# XBeeV2.net
KiCad netlist of a schematic drawn in EAGLE
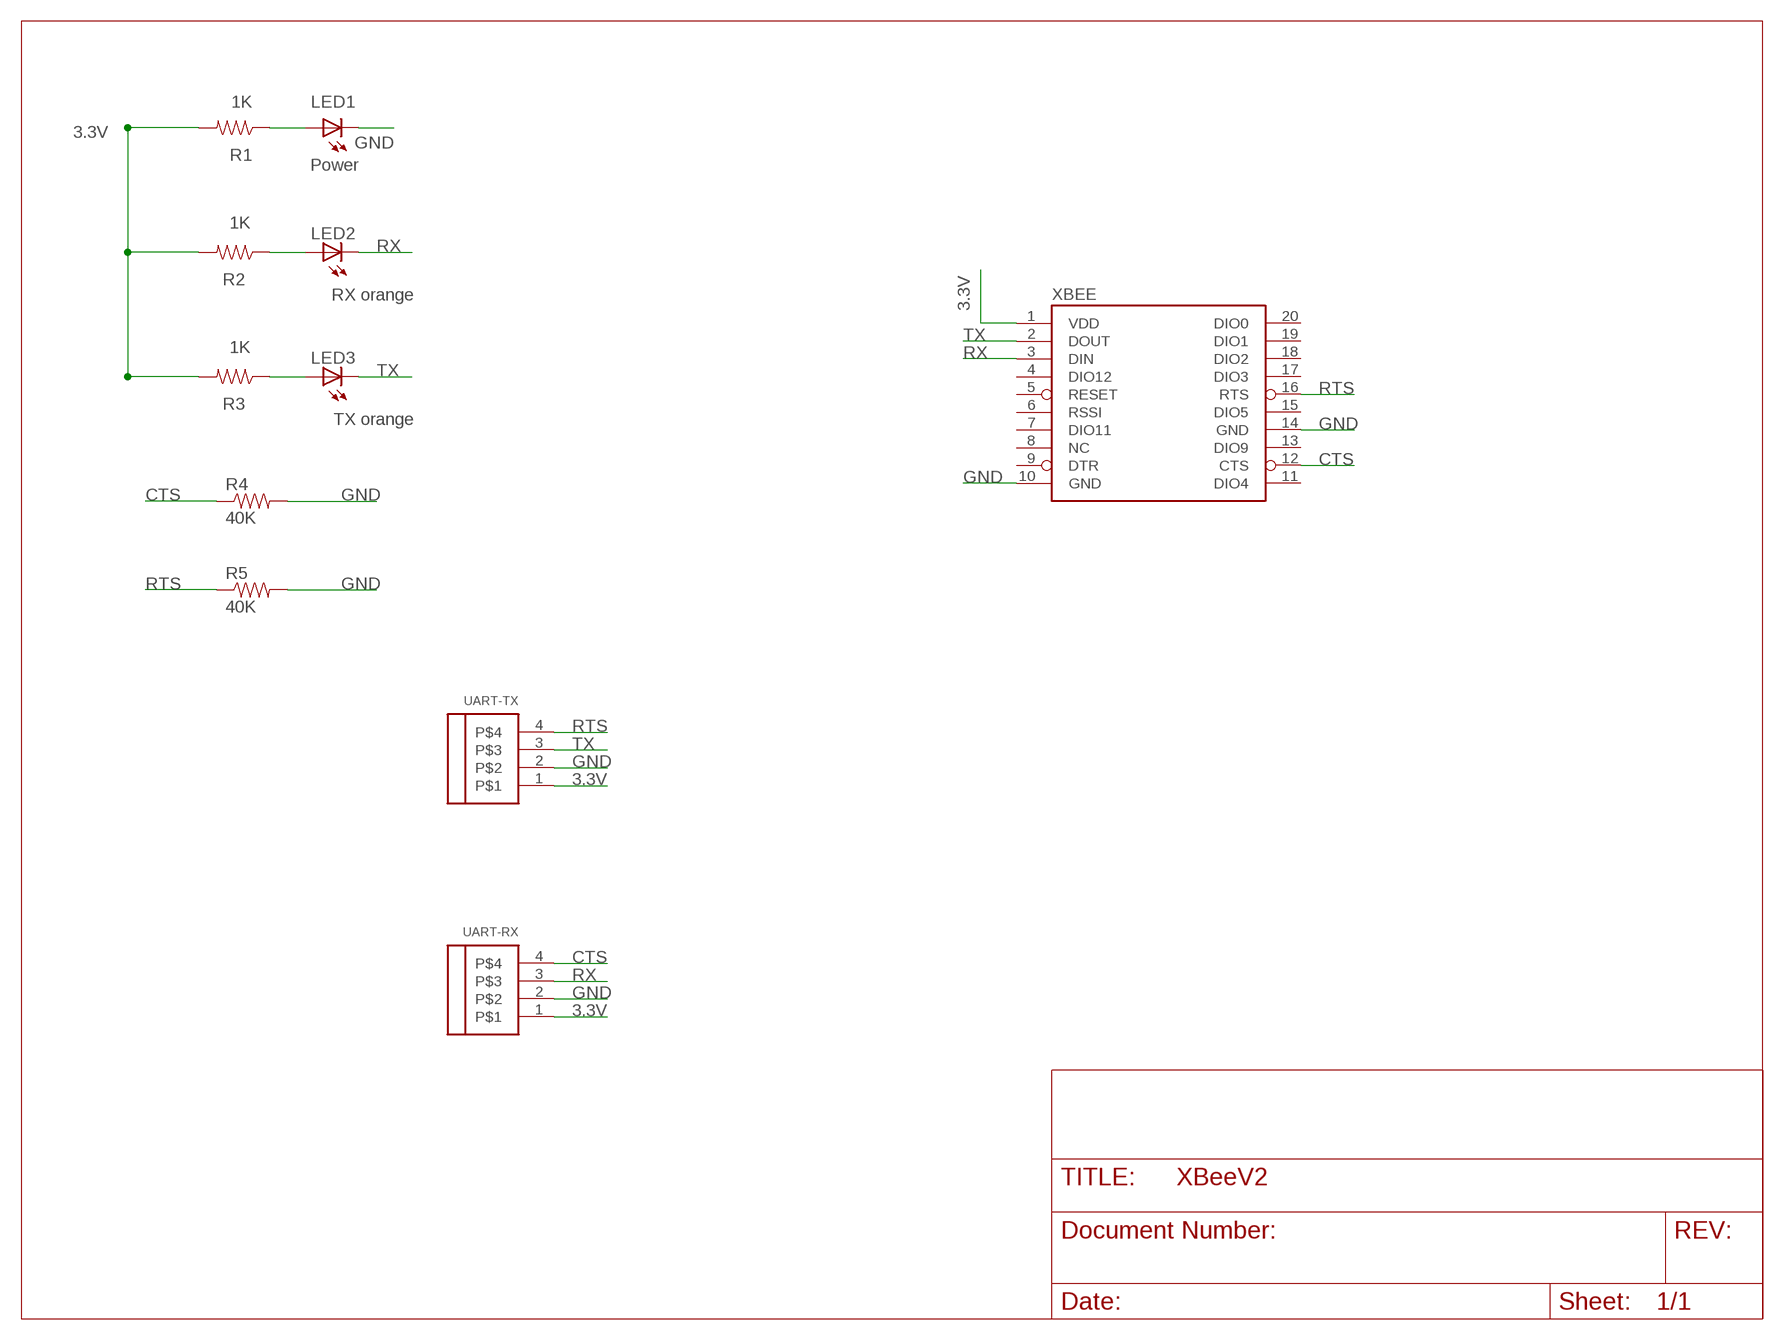
[diagram p0: schematic, sheet 1]

(export (version "E")
  (design (tool "Eeschema 10.0.6"))
  (components
    (comp (ref "LED1")
      (value "Power")
      (footprint "eagle-import:1206_INCH-HS-LED")
      (libsource (lib "eagle-import") (part "LED_SMD_1206"))
    )
    (comp (ref "LED2")
      (value "RX orange")
      (footprint "eagle-import:1206_INCH-HS-LED")
      (libsource (lib "eagle-import") (part "LED_SMD_1206"))
    )
    (comp (ref "LED3")
      (value "TX orange")
      (footprint "eagle-import:1206_INCH-HS-LED")
      (libsource (lib "eagle-import") (part "LED_SMD_1206"))
    )
    (comp (ref "R1")
      (value "1K")
      (footprint "eagle-import:0805_INCH-HS")
      (libsource (lib "eagle-import") (part "RESISTOR_0805"))
    )
    (comp (ref "R2")
      (value "1K")
      (footprint "eagle-import:0805_INCH-HS")
      (libsource (lib "eagle-import") (part "RESISTOR_0805"))
    )
    (comp (ref "R3")
      (value "1K")
      (footprint "eagle-import:0805_INCH-HS")
      (libsource (lib "eagle-import") (part "RESISTOR_0805"))
    )
    (comp (ref "R4")
      (value "40K")
      (footprint "eagle-import:0805_INCH-HS")
      (libsource (lib "eagle-import") (part "RESISTOR_0805"))
    )
    (comp (ref "R5")
      (value "40K")
      (footprint "eagle-import:0805_INCH-HS")
      (libsource (lib "eagle-import") (part "RESISTOR_0805"))
    )
    (comp (ref "UART-RX")
      (value "HEADER-04_JST-ZH_JST-ZH")
      (footprint "eagle-import:1X04-JST-ZH")
      (libsource (lib "eagle-import") (part "HEADER-04_JST-ZH_JST-ZH"))
    )
    (comp (ref "UART-TX")
      (value "HEADER-04_JST-ZH_JST-ZH")
      (footprint "eagle-import:1X04-JST-ZH")
      (libsource (lib "eagle-import") (part "HEADER-04_JST-ZH_JST-ZH"))
    )
    (comp (ref "XBEE")
      (value "XBEELOCK-SMALL-PRINT")
      (footprint "eagle-import:XBEE-1_LOCK")
      (libsource (lib "eagle-import") (part "XBEELOCK-SMALL-PRINT"))
    )
  )
  (nets
    (net (code "1") (name "/3.3V") (class "Default")
      (node (ref "R1") (pin "2") (pinfunction "2_2") (pintype "passive"))
      (node (ref "R2") (pin "2") (pinfunction "2_2") (pintype "passive"))
      (node (ref "R3") (pin "2") (pinfunction "2_2") (pintype "passive"))
      (node (ref "UART-RX") (pin "1") (pinfunction "P$1_1") (pintype "bidirectional"))
      (node (ref "UART-TX") (pin "1") (pinfunction "P$1_1") (pintype "bidirectional"))
      (node (ref "XBEE") (pin "1") (pinfunction "VDD_1") (pintype "power_in"))
    )
    (net (code "2") (name "/CTS") (class "Default")
      (node (ref "R4") (pin "1") (pinfunction "1_1") (pintype "passive"))
      (node (ref "UART-RX") (pin "4") (pinfunction "P$4_4") (pintype "bidirectional"))
      (node (ref "XBEE") (pin "12") (pinfunction "CTS_12") (pintype "output"))
    )
    (net (code "3") (name "/GND") (class "Default")
      (node (ref "LED1") (pin "C") (pinfunction "C_C") (pintype "passive"))
      (node (ref "R4") (pin "2") (pinfunction "2_2") (pintype "passive"))
      (node (ref "R5") (pin "2") (pinfunction "2_2") (pintype "passive"))
      (node (ref "UART-RX") (pin "2") (pinfunction "P$2_2") (pintype "bidirectional"))
      (node (ref "UART-TX") (pin "2") (pinfunction "P$2_2") (pintype "bidirectional"))
      (node (ref "XBEE") (pin "10") (pinfunction "GND_10") (pintype "power_in"))
      (node (ref "XBEE") (pin "14") (pinfunction "GND_14") (pintype "power_in"))
    )
    (net (code "4") (name "/RTS") (class "Default")
      (node (ref "R5") (pin "1") (pinfunction "1_1") (pintype "passive"))
      (node (ref "UART-TX") (pin "4") (pinfunction "P$4_4") (pintype "bidirectional"))
      (node (ref "XBEE") (pin "16") (pinfunction "RTS_16") (pintype "input"))
    )
    (net (code "5") (name "/RX") (class "Default")
      (node (ref "LED2") (pin "C") (pinfunction "C_C") (pintype "passive"))
      (node (ref "UART-RX") (pin "3") (pinfunction "P$3_3") (pintype "bidirectional"))
      (node (ref "XBEE") (pin "3") (pinfunction "DIN_3") (pintype "input"))
    )
    (net (code "6") (name "/TX") (class "Default")
      (node (ref "LED3") (pin "C") (pinfunction "C_C") (pintype "passive"))
      (node (ref "UART-TX") (pin "3") (pinfunction "P$3_3") (pintype "bidirectional"))
      (node (ref "XBEE") (pin "2") (pinfunction "DOUT_2") (pintype "output"))
    )
    (net (code "7") (name "Net-(LED1-PadA)") (class "Default")
      (node (ref "LED1") (pin "A") (pinfunction "A_A") (pintype "passive"))
      (node (ref "R1") (pin "1") (pinfunction "1_1") (pintype "passive"))
    )
    (net (code "8") (name "Net-(LED2-PadA)") (class "Default")
      (node (ref "LED2") (pin "A") (pinfunction "A_A") (pintype "passive"))
      (node (ref "R2") (pin "1") (pinfunction "1_1") (pintype "passive"))
    )
    (net (code "9") (name "Net-(LED3-PadA)") (class "Default")
      (node (ref "LED3") (pin "A") (pinfunction "A_A") (pintype "passive"))
      (node (ref "R3") (pin "1") (pinfunction "1_1") (pintype "passive"))
    )
    (net (code "10") (name "unconnected-(XBEE-DIO0-Pad20)") (class "Default")
      (node (ref "XBEE") (pin "20") (pinfunction "DIO0_20") (pintype "bidirectional"))
    )
    (net (code "11") (name "unconnected-(XBEE-DIO1-Pad19)") (class "Default")
      (node (ref "XBEE") (pin "19") (pinfunction "DIO1_19") (pintype "bidirectional"))
    )
    (net (code "12") (name "unconnected-(XBEE-DIO2-Pad18)") (class "Default")
      (node (ref "XBEE") (pin "18") (pinfunction "DIO2_18") (pintype "bidirectional"))
    )
    (net (code "13") (name "unconnected-(XBEE-DIO3-Pad17)") (class "Default")
      (node (ref "XBEE") (pin "17") (pinfunction "DIO3_17") (pintype "bidirectional"))
    )
    (net (code "14") (name "unconnected-(XBEE-DIO4-Pad11)") (class "Default")
      (node (ref "XBEE") (pin "11") (pinfunction "DIO4_11") (pintype "bidirectional"))
    )
    (net (code "15") (name "unconnected-(XBEE-DIO5-Pad15)") (class "Default")
      (node (ref "XBEE") (pin "15") (pinfunction "DIO5_15") (pintype "bidirectional"))
    )
    (net (code "16") (name "unconnected-(XBEE-DIO9-Pad13)") (class "Default")
      (node (ref "XBEE") (pin "13") (pinfunction "DIO9_13") (pintype "bidirectional"))
    )
    (net (code "17") (name "unconnected-(XBEE-DIO11-Pad7)") (class "Default")
      (node (ref "XBEE") (pin "7") (pinfunction "DIO11_7") (pintype "bidirectional"))
    )
    (net (code "18") (name "unconnected-(XBEE-DIO12-Pad4)") (class "Default")
      (node (ref "XBEE") (pin "4") (pinfunction "DIO12_4") (pintype "bidirectional"))
    )
    (net (code "19") (name "unconnected-(XBEE-DTR-Pad9)") (class "Default")
      (node (ref "XBEE") (pin "9") (pinfunction "DTR_9") (pintype "bidirectional"))
    )
    (net (code "20") (name "unconnected-(XBEE-NC-Pad8)") (class "Default")
      (node (ref "XBEE") (pin "8") (pinfunction "NC_8") (pintype "bidirectional"))
    )
    (net (code "21") (name "unconnected-(XBEE-RESET-Pad5)") (class "Default")
      (node (ref "XBEE") (pin "5") (pinfunction "RESET_5") (pintype "input"))
    )
    (net (code "22") (name "unconnected-(XBEE-RSSI-Pad6)") (class "Default")
      (node (ref "XBEE") (pin "6") (pinfunction "RSSI_6") (pintype "bidirectional"))
    )
  )
)
